# 5hp_proto.net
KiCad netlist of a schematic drawn in EAGLE
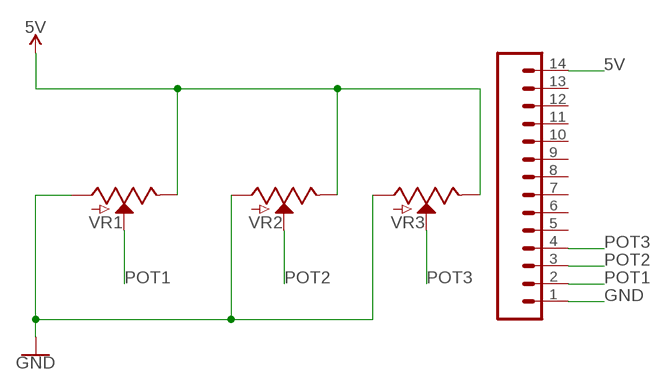
[diagram p0: schematic, sheet 1]

(export (version "E")
  (design (tool "Eeschema 10.0.6"))
  (components
    (comp (ref "J2")
      (value "CONN_14SQUARE")
      (footprint "eagle-import:1X14")
      (libsource (lib "eagle-import") (part "CONN_14SQUARE"))
    )
    (comp (ref "VR1")
      (value "POTENTIOMETERPOTV")
      (footprint "eagle-import:POT_V")
      (libsource (lib "eagle-import") (part "POTENTIOMETERPOTV"))
    )
    (comp (ref "VR2")
      (value "POTENTIOMETERPOTV")
      (footprint "eagle-import:POT_V")
      (libsource (lib "eagle-import") (part "POTENTIOMETERPOTV"))
    )
    (comp (ref "VR3")
      (value "POTENTIOMETERPOTV")
      (footprint "eagle-import:POT_V")
      (libsource (lib "eagle-import") (part "POTENTIOMETERPOTV"))
    )
  )
  (nets
    (net (code "1") (name "/POT1") (class "Default")
      (node (ref "J2") (pin "2") (pinfunction "2_2") (pintype "passive"))
      (node (ref "VR1") (pin "P2") (pinfunction "S_P2") (pintype "passive"))
    )
    (net (code "2") (name "/POT2") (class "Default")
      (node (ref "J2") (pin "3") (pinfunction "3_3") (pintype "passive"))
      (node (ref "VR2") (pin "P2") (pinfunction "S_P2") (pintype "passive"))
    )
    (net (code "3") (name "/POT3") (class "Default")
      (node (ref "J2") (pin "4") (pinfunction "4_4") (pintype "passive"))
      (node (ref "VR3") (pin "P2") (pinfunction "S_P2") (pintype "passive"))
    )
    (net (code "4") (name "5V") (class "Default")
      (node (ref "J2") (pin "14") (pinfunction "14_14") (pintype "passive"))
      (node (ref "VR1") (pin "P3") (pinfunction "E_P3") (pintype "passive"))
      (node (ref "VR2") (pin "P3") (pinfunction "E_P3") (pintype "passive"))
      (node (ref "VR3") (pin "P3") (pinfunction "E_P3") (pintype "passive"))
    )
    (net (code "5") (name "GND") (class "Default")
      (node (ref "J2") (pin "1") (pinfunction "1_1") (pintype "passive"))
      (node (ref "VR1") (pin "P1") (pinfunction "A_P1") (pintype "passive"))
      (node (ref "VR2") (pin "P1") (pinfunction "A_P1") (pintype "passive"))
      (node (ref "VR3") (pin "P1") (pinfunction "A_P1") (pintype "passive"))
    )
    (net (code "6") (name "unconnected-(J2-Pad5)") (class "Default")
      (node (ref "J2") (pin "5") (pinfunction "5_5") (pintype "passive"))
    )
    (net (code "7") (name "unconnected-(J2-Pad6)") (class "Default")
      (node (ref "J2") (pin "6") (pinfunction "6_6") (pintype "passive"))
    )
    (net (code "8") (name "unconnected-(J2-Pad7)") (class "Default")
      (node (ref "J2") (pin "7") (pinfunction "7_7") (pintype "passive"))
    )
    (net (code "9") (name "unconnected-(J2-Pad8)") (class "Default")
      (node (ref "J2") (pin "8") (pinfunction "8_8") (pintype "passive"))
    )
    (net (code "10") (name "unconnected-(J2-Pad9)") (class "Default")
      (node (ref "J2") (pin "9") (pinfunction "9_9") (pintype "passive"))
    )
    (net (code "11") (name "unconnected-(J2-Pad10)") (class "Default")
      (node (ref "J2") (pin "10") (pinfunction "10_10") (pintype "passive"))
    )
    (net (code "12") (name "unconnected-(J2-Pad11)") (class "Default")
      (node (ref "J2") (pin "11") (pinfunction "11_11") (pintype "passive"))
    )
    (net (code "13") (name "unconnected-(J2-Pad12)") (class "Default")
      (node (ref "J2") (pin "12") (pinfunction "12_12") (pintype "passive"))
    )
    (net (code "14") (name "unconnected-(J2-Pad13)") (class "Default")
      (node (ref "J2") (pin "13") (pinfunction "13_13") (pintype "passive"))
    )
  )
)
